# tec_controller_v4.net
KiCad netlist of a schematic drawn in EAGLE
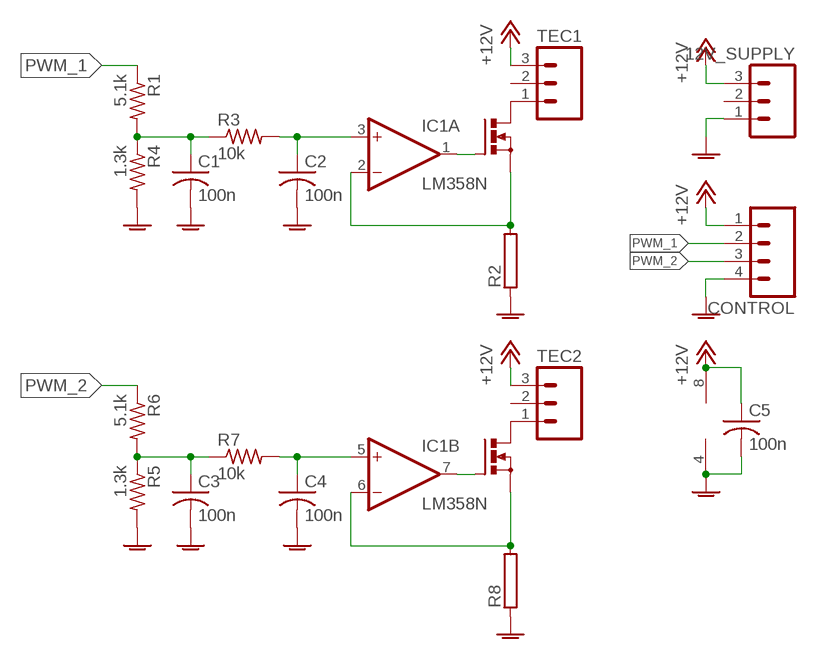
[diagram p0: schematic, sheet 1]

(export (version "E")
  (design (tool "Eeschema 10.0.6"))
  (components
    (comp (ref "12V_SUPPLY")
      (value "M03POLAR")
      (footprint "eagle-import:MOLEX-1X3")
      (libsource (lib "eagle-import") (part "M03POLAR"))
    )
    (comp (ref "C1")
      (value "100n")
      (footprint "eagle-import:C0805")
      (libsource (lib "eagle-import") (part "C-USC0805"))
    )
    (comp (ref "C2")
      (value "100n")
      (footprint "eagle-import:C0805")
      (libsource (lib "eagle-import") (part "C-USC0805"))
    )
    (comp (ref "C3")
      (value "100n")
      (footprint "eagle-import:C0805")
      (libsource (lib "eagle-import") (part "C-USC0805"))
    )
    (comp (ref "C4")
      (value "100n")
      (footprint "eagle-import:C0805")
      (libsource (lib "eagle-import") (part "C-USC0805"))
    )
    (comp (ref "C5")
      (value "100n")
      (footprint "eagle-import:C0805")
      (libsource (lib "eagle-import") (part "C-USC0805"))
    )
    (comp (ref "CONTROL")
      (value "M04POLAR")
      (footprint "eagle-import:MOLEX-1X4")
      (libsource (lib "eagle-import") (part "M04POLAR"))
    )
    (comp (ref "IC1")
      (value "LM358N")
      (footprint "eagle-import:DIL08")
      (libsource (lib "eagle-import") (part "LM358N"))
    )
    (comp (ref "Q1")
      (value "IRF512")
      (footprint "eagle-import:TO220BV")
      (libsource (lib "eagle-import") (part "IRF512"))
    )
    (comp (ref "Q2")
      (value "IRF512")
      (footprint "eagle-import:TO220BV")
      (libsource (lib "eagle-import") (part "IRF512"))
    )
    (comp (ref "R1")
      (value "5.1k")
      (footprint "eagle-import:M0805")
      (libsource (lib "eagle-import") (part "R-US_M0805"))
    )
    (comp (ref "R2")
      (value "RAC10")
      (footprint "eagle-import:AC10")
      (libsource (lib "eagle-import") (part "RAC10"))
    )
    (comp (ref "R3")
      (value "10k")
      (footprint "eagle-import:M0805")
      (libsource (lib "eagle-import") (part "R-US_M0805"))
    )
    (comp (ref "R4")
      (value "1.3k")
      (footprint "eagle-import:M0805")
      (libsource (lib "eagle-import") (part "R-US_M0805"))
    )
    (comp (ref "R5")
      (value "1.3k")
      (footprint "eagle-import:M0805")
      (libsource (lib "eagle-import") (part "R-US_M0805"))
    )
    (comp (ref "R6")
      (value "5.1k")
      (footprint "eagle-import:M0805")
      (libsource (lib "eagle-import") (part "R-US_M0805"))
    )
    (comp (ref "R7")
      (value "10k")
      (footprint "eagle-import:M0805")
      (libsource (lib "eagle-import") (part "R-US_M0805"))
    )
    (comp (ref "R8")
      (value "RAC10")
      (footprint "eagle-import:AC10")
      (libsource (lib "eagle-import") (part "RAC10"))
    )
    (comp (ref "TEC1")
      (value "M03POLAR")
      (footprint "eagle-import:MOLEX-1X3")
      (libsource (lib "eagle-import") (part "M03POLAR"))
    )
    (comp (ref "TEC2")
      (value "M03POLAR")
      (footprint "eagle-import:MOLEX-1X3")
      (libsource (lib "eagle-import") (part "M03POLAR"))
    )
  )
  (nets
    (net (code "1") (name "+12V") (class "Default")
      (node (ref "12V_SUPPLY") (pin "3") (pinfunction "3_3") (pintype "passive"))
      (node (ref "C5") (pin "1") (pinfunction "1_1") (pintype "passive"))
      (node (ref "CONTROL") (pin "1") (pinfunction "1_1") (pintype "passive"))
      (node (ref "IC1") (pin "8") (pinfunction "V+_8") (pintype "power_in"))
      (node (ref "TEC1") (pin "3") (pinfunction "3_3") (pintype "passive"))
      (node (ref "TEC2") (pin "3") (pinfunction "3_3") (pintype "passive"))
    )
    (net (code "2") (name "GNDA") (class "Default")
      (node (ref "12V_SUPPLY") (pin "1") (pinfunction "1_1") (pintype "passive"))
      (node (ref "C1") (pin "2") (pinfunction "2_2") (pintype "passive"))
      (node (ref "C2") (pin "2") (pinfunction "2_2") (pintype "passive"))
      (node (ref "C3") (pin "2") (pinfunction "2_2") (pintype "passive"))
      (node (ref "C4") (pin "2") (pinfunction "2_2") (pintype "passive"))
      (node (ref "C5") (pin "2") (pinfunction "2_2") (pintype "passive"))
      (node (ref "CONTROL") (pin "4") (pinfunction "4_4") (pintype "passive"))
      (node (ref "IC1") (pin "4") (pinfunction "V-_4") (pintype "power_in"))
      (node (ref "R2") (pin "1") (pinfunction "1_1") (pintype "passive"))
      (node (ref "R4") (pin "2") (pinfunction "2_2") (pintype "passive"))
      (node (ref "R5") (pin "2") (pinfunction "2_2") (pintype "passive"))
      (node (ref "R8") (pin "1") (pinfunction "1_1") (pintype "passive"))
    )
    (net (code "3") (name "Net-(C1-Pad1)") (class "Default")
      (node (ref "C1") (pin "1") (pinfunction "1_1") (pintype "passive"))
      (node (ref "R1") (pin "2") (pinfunction "2_2") (pintype "passive"))
      (node (ref "R3") (pin "1") (pinfunction "1_1") (pintype "passive"))
      (node (ref "R4") (pin "1") (pinfunction "1_1") (pintype "passive"))
    )
    (net (code "4") (name "Net-(C3-Pad1)") (class "Default")
      (node (ref "C3") (pin "1") (pinfunction "1_1") (pintype "passive"))
      (node (ref "R5") (pin "1") (pinfunction "1_1") (pintype "passive"))
      (node (ref "R6") (pin "2") (pinfunction "2_2") (pintype "passive"))
      (node (ref "R7") (pin "1") (pinfunction "1_1") (pintype "passive"))
    )
    (net (code "5") (name "Net-(IC1A-+IN)") (class "Default")
      (node (ref "C2") (pin "1") (pinfunction "1_1") (pintype "passive"))
      (node (ref "IC1") (pin "3") (pinfunction "+IN_3") (pintype "input"))
      (node (ref "R3") (pin "2") (pinfunction "2_2") (pintype "passive"))
    )
    (net (code "6") (name "Net-(IC1A--IN)") (class "Default")
      (node (ref "IC1") (pin "2") (pinfunction "-IN_2") (pintype "input"))
      (node (ref "Q1") (pin "S") (pinfunction "S_S") (pintype "passive"))
      (node (ref "R2") (pin "2") (pinfunction "2_2") (pintype "passive"))
    )
    (net (code "7") (name "Net-(IC1A-OUT)") (class "Default")
      (node (ref "IC1") (pin "1") (pinfunction "OUT_1") (pintype "output"))
      (node (ref "Q1") (pin "G") (pinfunction "G_G") (pintype "passive"))
    )
    (net (code "8") (name "Net-(IC1B-+IN)") (class "Default")
      (node (ref "C4") (pin "1") (pinfunction "1_1") (pintype "passive"))
      (node (ref "IC1") (pin "5") (pinfunction "+IN_5") (pintype "input"))
      (node (ref "R7") (pin "2") (pinfunction "2_2") (pintype "passive"))
    )
    (net (code "9") (name "Net-(IC1B--IN)") (class "Default")
      (node (ref "IC1") (pin "6") (pinfunction "-IN_6") (pintype "input"))
      (node (ref "Q2") (pin "S") (pinfunction "S_S") (pintype "passive"))
      (node (ref "R8") (pin "2") (pinfunction "2_2") (pintype "passive"))
    )
    (net (code "10") (name "Net-(IC1B-OUT)") (class "Default")
      (node (ref "IC1") (pin "7") (pinfunction "OUT_7") (pintype "output"))
      (node (ref "Q2") (pin "G") (pinfunction "G_G") (pintype "passive"))
    )
    (net (code "11") (name "Net-(Q1-PadD)") (class "Default")
      (node (ref "Q1") (pin "D") (pinfunction "D_D") (pintype "passive"))
      (node (ref "TEC1") (pin "1") (pinfunction "1_1") (pintype "passive"))
    )
    (net (code "12") (name "Net-(Q2-PadD)") (class "Default")
      (node (ref "Q2") (pin "D") (pinfunction "D_D") (pintype "passive"))
      (node (ref "TEC2") (pin "1") (pinfunction "1_1") (pintype "passive"))
    )
    (net (code "13") (name "PWM_1") (class "Default")
      (node (ref "CONTROL") (pin "2") (pinfunction "2_2") (pintype "passive"))
      (node (ref "R1") (pin "1") (pinfunction "1_1") (pintype "passive"))
    )
    (net (code "14") (name "PWM_2") (class "Default")
      (node (ref "CONTROL") (pin "3") (pinfunction "3_3") (pintype "passive"))
      (node (ref "R6") (pin "1") (pinfunction "1_1") (pintype "passive"))
    )
    (net (code "15") (name "unconnected-(12V_SUPPLY-Pad2)") (class "Default")
      (node (ref "12V_SUPPLY") (pin "2") (pinfunction "2_2") (pintype "passive"))
    )
    (net (code "16") (name "unconnected-(TEC1-Pad2)") (class "Default")
      (node (ref "TEC1") (pin "2") (pinfunction "2_2") (pintype "passive"))
    )
    (net (code "17") (name "unconnected-(TEC2-Pad2)") (class "Default")
      (node (ref "TEC2") (pin "2") (pinfunction "2_2") (pintype "passive"))
    )
  )
)
